# Connector_Section.net
KiCad netlist of a schematic drawn in Altium Designer
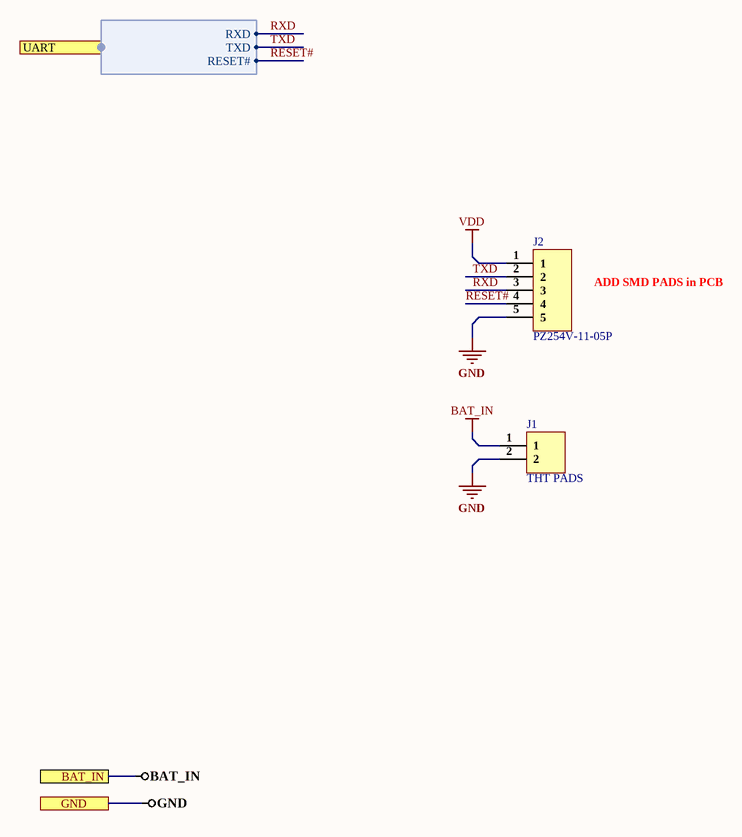
[diagram p0: Connector Section.SchDoc]

(export (version "E")
  (design (tool "Eeschema 10.0.6"))
  (components
    (comp (ref "J1") (value "THT PADS") (footprint "THT PAD") (libsource (lib "TT_IntLib") (part "THT PAD")))
    (comp (ref "J2")
      (value "PZ254V-11-05P")
      (footprint "PZ254V-11-05P")
      (description "Pin Header 5 1 right-angle")
      (fields (field (name "MANUFACTURER") "XFCN"))
      (libsource (lib "TT_IntLib") (part "PZ254V-11-05P"))
    )
  )
  (nets
    (net (code "2") (name "/RESET#") (class "Default")
      (node (ref "J2") (pin "4") (pinfunction "4_4") (pintype "passive"))
    )
    (net (code "3") (name "/RXD") (class "Default")
      (node (ref "J2") (pin "3") (pinfunction "3_3") (pintype "passive"))
    )
    (net (code "4") (name "/TXD") (class "Default")
      (node (ref "J2") (pin "2") (pinfunction "2_2") (pintype "passive"))
    )
    (net (code "6") (name "BAT_IN") (class "Default")
      (node (ref "J1") (pin "1") (pinfunction "1_1") (pintype "passive"))
    )
    (net (code "7") (name "GND") (class "Default")
      (node (ref "J1") (pin "2") (pinfunction "2_2") (pintype "passive"))
      (node (ref "J2") (pin "5") (pinfunction "5_5") (pintype "passive"))
    )
    (net (code "8") (name "VDD") (class "Default")
      (node (ref "J2") (pin "1") (pinfunction "1_1") (pintype "passive"))
    )
  )
)
